# J3.net
KiCad netlist of a schematic drawn in Altium Designer
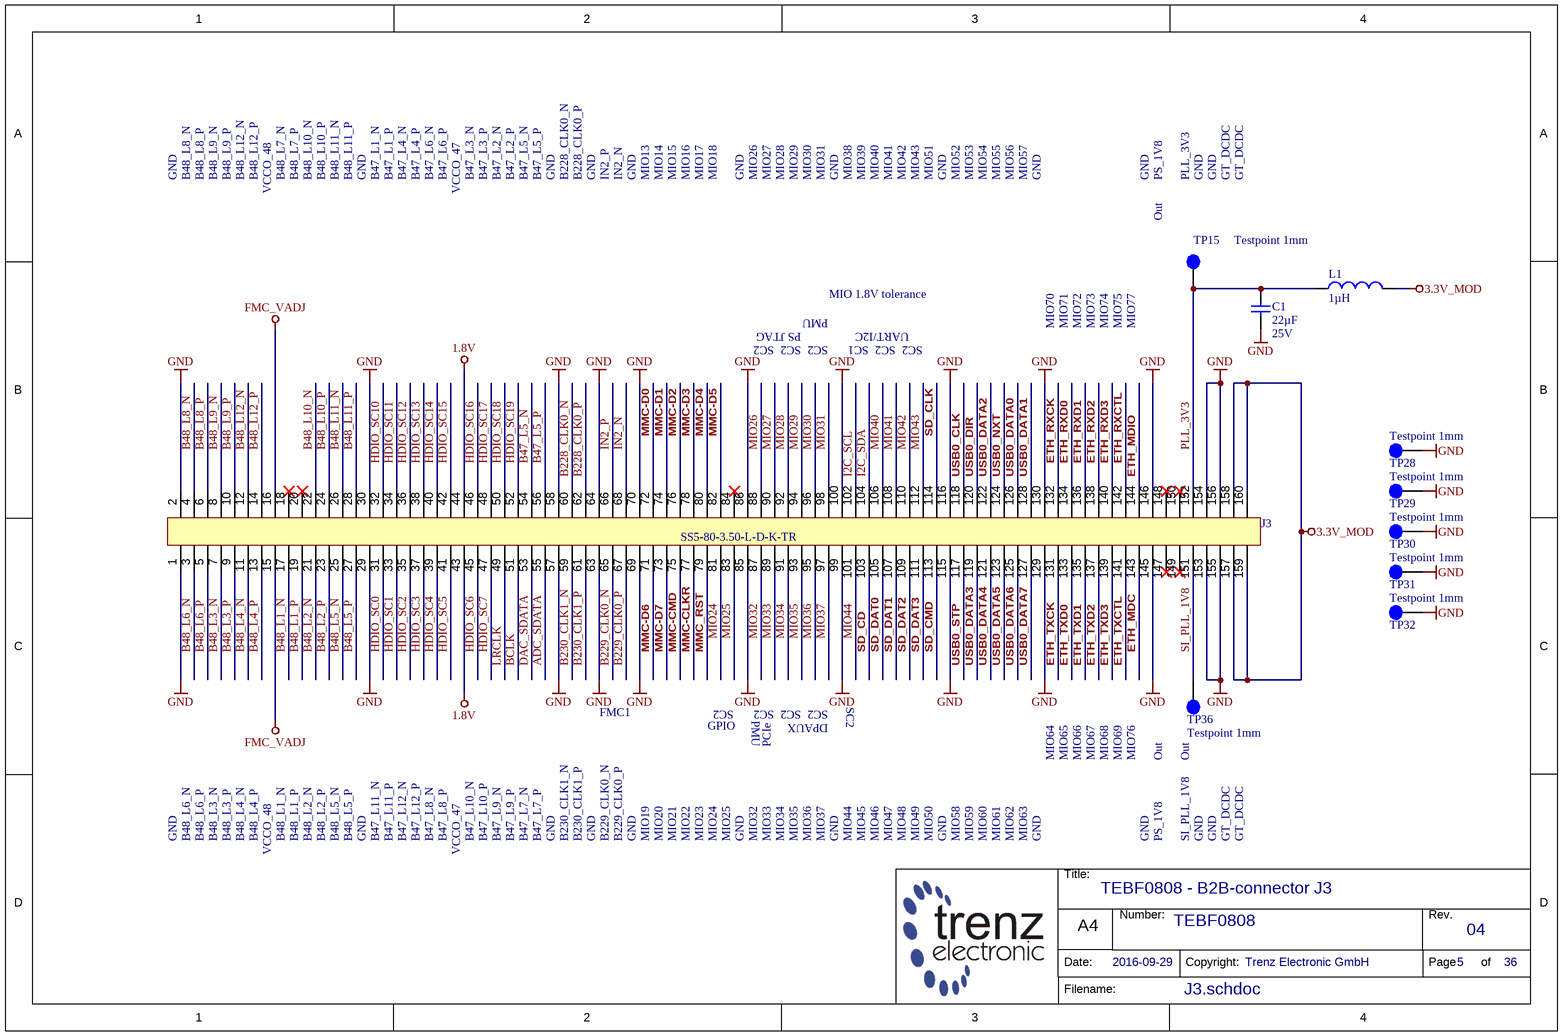
[diagram p0: J3.schdoc]

(export (version "E")
  (design (tool "Eeschema 10.0.6"))
  (components
    (comp (ref "C1")
      (value "22µF")
      (footprint "CAPC3216X180N")
      (description "KON 22µF X5R 25V SMD 10%")
      (fields (field (name "VOLTAGE") "25V") (field (name "TOLERANCE") "10%"))
      (libsource (lib "TE") (part "CAP-NP"))
    )
    (comp (ref "J3")
      (value "SS5-80-3.50-L-D-K-TR")
      (footprint "SS5-80-3.50-L-D-K-TR")
      (description "Samtec Ultra Fine Pitch Socket REF192552-01, 160 Pins")
      (libsource (lib "TE") (part "CON-160"))
    )
    (comp (ref "L1")
      (value "1µH")
      (footprint "INDC2520X100N")
      (description "IND SMD 1µH +-20% 0.055Ohm")
      (fields (field (name "VOLTAGE") "1.7A"))
      (libsource (lib "TE") (part "IND"))
    )
    (comp (ref "TP15") (value "Testpoint 1mm") (footprint "TP_1mm") (libsource (lib "TE") (part "TP")))
    (comp (ref "TP28") (value "Testpoint 1mm") (footprint "TP_1mm") (libsource (lib "TE") (part "TP")))
    (comp (ref "TP29") (value "Testpoint 1mm") (footprint "TP_1mm") (libsource (lib "TE") (part "TP")))
    (comp (ref "TP30") (value "Testpoint 1mm") (footprint "TP_1mm") (libsource (lib "TE") (part "TP")))
    (comp (ref "TP31") (value "Testpoint 1mm") (footprint "TP_1mm") (libsource (lib "TE") (part "TP")))
    (comp (ref "TP32") (value "Testpoint 1mm") (footprint "TP_1mm") (libsource (lib "TE") (part "TP")))
    (comp (ref "TP36") (value "Testpoint 1mm") (footprint "TP_1mm") (libsource (lib "TE") (part "TP")))
  )
  (nets
    (net (code "1") (name "/ADC_SDATA") (class "Default")
      (node (ref "J3") (pin "55") (pinfunction "55_55") (pintype "passive"))
    )
    (net (code "2") (name "/B47_L5_N") (class "Default")
      (node (ref "J3") (pin "54") (pinfunction "54_54") (pintype "passive"))
    )
    (net (code "3") (name "/B47_L5_P") (class "Default")
      (node (ref "J3") (pin "56") (pinfunction "56_56") (pintype "passive"))
    )
    (net (code "4") (name "/B48_L1_N") (class "Default")
      (node (ref "J3") (pin "17") (pinfunction "17_17") (pintype "passive"))
    )
    (net (code "5") (name "/B48_L1_P") (class "Default")
      (node (ref "J3") (pin "19") (pinfunction "19_19") (pintype "passive"))
    )
    (net (code "6") (name "/B48_L2_N") (class "Default")
      (node (ref "J3") (pin "21") (pinfunction "21_21") (pintype "passive"))
    )
    (net (code "7") (name "/B48_L2_P") (class "Default")
      (node (ref "J3") (pin "23") (pinfunction "23_23") (pintype "passive"))
    )
    (net (code "8") (name "/B48_L3_N") (class "Default")
      (node (ref "J3") (pin "7") (pinfunction "7_7") (pintype "passive"))
    )
    (net (code "9") (name "/B48_L3_P") (class "Default")
      (node (ref "J3") (pin "9") (pinfunction "9_9") (pintype "passive"))
    )
    (net (code "10") (name "/B48_L4_N") (class "Default")
      (node (ref "J3") (pin "11") (pinfunction "11_11") (pintype "passive"))
    )
    (net (code "11") (name "/B48_L4_P") (class "Default")
      (node (ref "J3") (pin "13") (pinfunction "13_13") (pintype "passive"))
    )
    (net (code "12") (name "/B48_L5_N") (class "Default")
      (node (ref "J3") (pin "25") (pinfunction "25_25") (pintype "passive"))
    )
    (net (code "13") (name "/B48_L5_P") (class "Default")
      (node (ref "J3") (pin "27") (pinfunction "27_27") (pintype "passive"))
    )
    (net (code "14") (name "/B48_L6_N") (class "Default")
      (node (ref "J3") (pin "3") (pinfunction "3_3") (pintype "passive"))
    )
    (net (code "15") (name "/B48_L6_P") (class "Default")
      (node (ref "J3") (pin "5") (pinfunction "5_5") (pintype "passive"))
    )
    (net (code "16") (name "/B48_L8_N") (class "Default")
      (node (ref "J3") (pin "4") (pinfunction "4_4") (pintype "passive"))
    )
    (net (code "17") (name "/B48_L8_P") (class "Default")
      (node (ref "J3") (pin "6") (pinfunction "6_6") (pintype "passive"))
    )
    (net (code "18") (name "/B48_L9_N") (class "Default")
      (node (ref "J3") (pin "8") (pinfunction "8_8") (pintype "passive"))
    )
    (net (code "19") (name "/B48_L9_P") (class "Default")
      (node (ref "J3") (pin "10") (pinfunction "10_10") (pintype "passive"))
    )
    (net (code "20") (name "/B48_L10_N") (class "Default")
      (node (ref "J3") (pin "22") (pinfunction "22_22") (pintype "passive"))
    )
    (net (code "21") (name "/B48_L10_P") (class "Default")
      (node (ref "J3") (pin "24") (pinfunction "24_24") (pintype "passive"))
    )
    (net (code "22") (name "/B48_L11_N") (class "Default")
      (node (ref "J3") (pin "26") (pinfunction "26_26") (pintype "passive"))
    )
    (net (code "23") (name "/B48_L11_P") (class "Default")
      (node (ref "J3") (pin "28") (pinfunction "28_28") (pintype "passive"))
    )
    (net (code "24") (name "/B48_L12_N") (class "Default")
      (node (ref "J3") (pin "12") (pinfunction "12_12") (pintype "passive"))
    )
    (net (code "25") (name "/B48_L12_P") (class "Default")
      (node (ref "J3") (pin "14") (pinfunction "14_14") (pintype "passive"))
    )
    (net (code "26") (name "/B228_CLK0_N") (class "Default")
      (node (ref "J3") (pin "60") (pinfunction "60_60") (pintype "passive"))
    )
    (net (code "27") (name "/B228_CLK0_P") (class "Default")
      (node (ref "J3") (pin "62") (pinfunction "62_62") (pintype "passive"))
    )
    (net (code "28") (name "/B229_CLK0_N") (class "Default")
      (node (ref "J3") (pin "65") (pinfunction "65_65") (pintype "passive"))
    )
    (net (code "29") (name "/B229_CLK0_P") (class "Default")
      (node (ref "J3") (pin "67") (pinfunction "67_67") (pintype "passive"))
    )
    (net (code "30") (name "/B230_CLK1_N") (class "Default")
      (node (ref "J3") (pin "59") (pinfunction "59_59") (pintype "passive"))
    )
    (net (code "31") (name "/B230_CLK1_P") (class "Default")
      (node (ref "J3") (pin "61") (pinfunction "61_61") (pintype "passive"))
    )
    (net (code "32") (name "/BCLK") (class "Default")
      (node (ref "J3") (pin "51") (pinfunction "51_51") (pintype "passive"))
    )
    (net (code "33") (name "/DAC_SDATA") (class "Default")
      (node (ref "J3") (pin "53") (pinfunction "53_53") (pintype "passive"))
    )
    (net (code "34") (name "/ETH_MDC") (class "Default")
      (node (ref "J3") (pin "143") (pinfunction "143_143") (pintype "passive"))
    )
    (net (code "35") (name "/ETH_MDIO") (class "Default")
      (node (ref "J3") (pin "144") (pinfunction "144_144") (pintype "passive"))
    )
    (net (code "36") (name "/ETH_RXCK") (class "Default")
      (node (ref "J3") (pin "132") (pinfunction "132_132") (pintype "passive"))
    )
    (net (code "37") (name "/ETH_RXCTL") (class "Default")
      (node (ref "J3") (pin "142") (pinfunction "142_142") (pintype "passive"))
    )
    (net (code "38") (name "/ETH_RXD0") (class "Default")
      (node (ref "J3") (pin "134") (pinfunction "134_134") (pintype "passive"))
    )
    (net (code "39") (name "/ETH_RXD1") (class "Default")
      (node (ref "J3") (pin "136") (pinfunction "136_136") (pintype "passive"))
    )
    (net (code "40") (name "/ETH_RXD2") (class "Default")
      (node (ref "J3") (pin "138") (pinfunction "138_138") (pintype "passive"))
    )
    (net (code "41") (name "/ETH_RXD3") (class "Default")
      (node (ref "J3") (pin "140") (pinfunction "140_140") (pintype "passive"))
    )
    (net (code "42") (name "/ETH_TXCK") (class "Default")
      (node (ref "J3") (pin "131") (pinfunction "131_131") (pintype "passive"))
    )
    (net (code "43") (name "/ETH_TXCTL") (class "Default")
      (node (ref "J3") (pin "141") (pinfunction "141_141") (pintype "passive"))
    )
    (net (code "44") (name "/ETH_TXD0") (class "Default")
      (node (ref "J3") (pin "133") (pinfunction "133_133") (pintype "passive"))
    )
    (net (code "45") (name "/ETH_TXD1") (class "Default")
      (node (ref "J3") (pin "135") (pinfunction "135_135") (pintype "passive"))
    )
    (net (code "46") (name "/ETH_TXD2") (class "Default")
      (node (ref "J3") (pin "137") (pinfunction "137_137") (pintype "passive"))
    )
    (net (code "47") (name "/ETH_TXD3") (class "Default")
      (node (ref "J3") (pin "139") (pinfunction "139_139") (pintype "passive"))
    )
    (net (code "48") (name "/HDIO_SC0") (class "Default")
      (node (ref "J3") (pin "31") (pinfunction "31_31") (pintype "passive"))
    )
    (net (code "49") (name "/HDIO_SC1") (class "Default")
      (node (ref "J3") (pin "33") (pinfunction "33_33") (pintype "passive"))
    )
    (net (code "50") (name "/HDIO_SC2") (class "Default")
      (node (ref "J3") (pin "35") (pinfunction "35_35") (pintype "passive"))
    )
    (net (code "51") (name "/HDIO_SC3") (class "Default")
      (node (ref "J3") (pin "37") (pinfunction "37_37") (pintype "passive"))
    )
    (net (code "52") (name "/HDIO_SC4") (class "Default")
      (node (ref "J3") (pin "39") (pinfunction "39_39") (pintype "passive"))
    )
    (net (code "53") (name "/HDIO_SC5") (class "Default")
      (node (ref "J3") (pin "41") (pinfunction "41_41") (pintype "passive"))
    )
    (net (code "54") (name "/HDIO_SC6") (class "Default")
      (node (ref "J3") (pin "45") (pinfunction "45_45") (pintype "passive"))
    )
    (net (code "55") (name "/HDIO_SC7") (class "Default")
      (node (ref "J3") (pin "47") (pinfunction "47_47") (pintype "passive"))
    )
    (net (code "56") (name "/HDIO_SC10") (class "Default")
      (node (ref "J3") (pin "32") (pinfunction "32_32") (pintype "passive"))
    )
    (net (code "57") (name "/HDIO_SC11") (class "Default")
      (node (ref "J3") (pin "34") (pinfunction "34_34") (pintype "passive"))
    )
    (net (code "58") (name "/HDIO_SC12") (class "Default")
      (node (ref "J3") (pin "36") (pinfunction "36_36") (pintype "passive"))
    )
    (net (code "59") (name "/HDIO_SC13") (class "Default")
      (node (ref "J3") (pin "38") (pinfunction "38_38") (pintype "passive"))
    )
    (net (code "60") (name "/HDIO_SC14") (class "Default")
      (node (ref "J3") (pin "40") (pinfunction "40_40") (pintype "passive"))
    )
    (net (code "61") (name "/HDIO_SC15") (class "Default")
      (node (ref "J3") (pin "42") (pinfunction "42_42") (pintype "passive"))
    )
    (net (code "62") (name "/HDIO_SC16") (class "Default")
      (node (ref "J3") (pin "46") (pinfunction "46_46") (pintype "passive"))
    )
    (net (code "63") (name "/HDIO_SC17") (class "Default")
      (node (ref "J3") (pin "48") (pinfunction "48_48") (pintype "passive"))
    )
    (net (code "64") (name "/HDIO_SC18") (class "Default")
      (node (ref "J3") (pin "50") (pinfunction "50_50") (pintype "passive"))
    )
    (net (code "65") (name "/HDIO_SC19") (class "Default")
      (node (ref "J3") (pin "52") (pinfunction "52_52") (pintype "passive"))
    )
    (net (code "66") (name "/I2C_SCL") (class "Default")
      (node (ref "J3") (pin "102") (pinfunction "102_102") (pintype "passive"))
    )
    (net (code "67") (name "/I2C_SDA") (class "Default")
      (node (ref "J3") (pin "104") (pinfunction "104_104") (pintype "passive"))
    )
    (net (code "68") (name "/IN2_N") (class "Default")
      (node (ref "J3") (pin "68") (pinfunction "68_68") (pintype "passive"))
    )
    (net (code "69") (name "/IN2_P") (class "Default")
      (node (ref "J3") (pin "66") (pinfunction "66_66") (pintype "passive"))
    )
    (net (code "70") (name "/LRCLK") (class "Default")
      (node (ref "J3") (pin "49") (pinfunction "49_49") (pintype "passive"))
    )
    (net (code "71") (name "/MIO24") (class "Default")
      (node (ref "J3") (pin "81") (pinfunction "81_81") (pintype "passive"))
    )
    (net (code "72") (name "/MIO25") (class "Default")
      (node (ref "J3") (pin "83") (pinfunction "83_83") (pintype "passive"))
    )
    (net (code "73") (name "/MIO26") (class "Default")
      (node (ref "J3") (pin "88") (pinfunction "88_88") (pintype "passive"))
    )
    (net (code "74") (name "/MIO27") (class "Default")
      (node (ref "J3") (pin "90") (pinfunction "90_90") (pintype "passive"))
    )
    (net (code "75") (name "/MIO28") (class "Default")
      (node (ref "J3") (pin "92") (pinfunction "92_92") (pintype "passive"))
    )
    (net (code "76") (name "/MIO29") (class "Default")
      (node (ref "J3") (pin "94") (pinfunction "94_94") (pintype "passive"))
    )
    (net (code "77") (name "/MIO30") (class "Default")
      (node (ref "J3") (pin "96") (pinfunction "96_96") (pintype "passive"))
    )
    (net (code "78") (name "/MIO31") (class "Default")
      (node (ref "J3") (pin "98") (pinfunction "98_98") (pintype "passive"))
    )
    (net (code "79") (name "/MIO32") (class "Default")
      (node (ref "J3") (pin "87") (pinfunction "87_87") (pintype "passive"))
    )
    (net (code "80") (name "/MIO33") (class "Default")
      (node (ref "J3") (pin "89") (pinfunction "89_89") (pintype "passive"))
    )
    (net (code "81") (name "/MIO34") (class "Default")
      (node (ref "J3") (pin "91") (pinfunction "91_91") (pintype "passive"))
    )
    (net (code "82") (name "/MIO35") (class "Default")
      (node (ref "J3") (pin "93") (pinfunction "93_93") (pintype "passive"))
    )
    (net (code "83") (name "/MIO36") (class "Default")
      (node (ref "J3") (pin "95") (pinfunction "95_95") (pintype "passive"))
    )
    (net (code "84") (name "/MIO37") (class "Default")
      (node (ref "J3") (pin "97") (pinfunction "97_97") (pintype "passive"))
    )
    (net (code "85") (name "/MIO40") (class "Default")
      (node (ref "J3") (pin "106") (pinfunction "106_106") (pintype "passive"))
    )
    (net (code "86") (name "/MIO41") (class "Default")
      (node (ref "J3") (pin "108") (pinfunction "108_108") (pintype "passive"))
    )
    (net (code "87") (name "/MIO42") (class "Default")
      (node (ref "J3") (pin "110") (pinfunction "110_110") (pintype "passive"))
    )
    (net (code "88") (name "/MIO43") (class "Default")
      (node (ref "J3") (pin "112") (pinfunction "112_112") (pintype "passive"))
    )
    (net (code "89") (name "/MIO44") (class "Default")
      (node (ref "J3") (pin "101") (pinfunction "101_101") (pintype "passive"))
    )
    (net (code "90") (name "/MMC-CLKR") (class "Default")
      (node (ref "J3") (pin "77") (pinfunction "77_77") (pintype "passive"))
    )
    (net (code "91") (name "/MMC-CMD") (class "Default")
      (node (ref "J3") (pin "75") (pinfunction "75_75") (pintype "passive"))
    )
    (net (code "92") (name "/MMC-D0") (class "Default")
      (node (ref "J3") (pin "72") (pinfunction "72_72") (pintype "passive"))
    )
    (net (code "93") (name "/MMC-D1") (class "Default")
      (node (ref "J3") (pin "74") (pinfunction "74_74") (pintype "passive"))
    )
    (net (code "94") (name "/MMC-D2") (class "Default")
      (node (ref "J3") (pin "76") (pinfunction "76_76") (pintype "passive"))
    )
    (net (code "95") (name "/MMC-D3") (class "Default")
      (node (ref "J3") (pin "78") (pinfunction "78_78") (pintype "passive"))
    )
    (net (code "96") (name "/MMC-D4") (class "Default")
      (node (ref "J3") (pin "80") (pinfunction "80_80") (pintype "passive"))
    )
    (net (code "97") (name "/MMC-D5") (class "Default")
      (node (ref "J3") (pin "82") (pinfunction "82_82") (pintype "passive"))
    )
    (net (code "98") (name "/MMC-D6") (class "Default")
      (node (ref "J3") (pin "71") (pinfunction "71_71") (pintype "passive"))
    )
    (net (code "99") (name "/MMC-D7") (class "Default")
      (node (ref "J3") (pin "73") (pinfunction "73_73") (pintype "passive"))
    )
    (net (code "100") (name "/MMC_RST") (class "Default")
      (node (ref "J3") (pin "79") (pinfunction "79_79") (pintype "passive"))
    )
    (net (code "101") (name "/PLL_3V3") (class "Default")
      (node (ref "C1") (pin "2") (pinfunction "2_2") (pintype "passive"))
      (node (ref "J3") (pin "152") (pinfunction "152_152") (pintype "passive"))
      (node (ref "L1") (pin "1") (pinfunction "1_1") (pintype "passive"))
      (node (ref "TP15") (pin "1") (pintype "passive"))
    )
    (net (code "102") (name "/SD_CD") (class "Default")
      (node (ref "J3") (pin "103") (pinfunction "103_103") (pintype "passive"))
    )
    (net (code "103") (name "/SD_CLK") (class "Default")
      (node (ref "J3") (pin "114") (pinfunction "114_114") (pintype "passive"))
    )
    (net (code "104") (name "/SD_CMD") (class "Default")
      (node (ref "J3") (pin "113") (pinfunction "113_113") (pintype "passive"))
    )
    (net (code "105") (name "/SD_DAT0") (class "Default")
      (node (ref "J3") (pin "105") (pinfunction "105_105") (pintype "passive"))
    )
    (net (code "106") (name "/SD_DAT1") (class "Default")
      (node (ref "J3") (pin "107") (pinfunction "107_107") (pintype "passive"))
    )
    (net (code "107") (name "/SD_DAT2") (class "Default")
      (node (ref "J3") (pin "109") (pinfunction "109_109") (pintype "passive"))
    )
    (net (code "108") (name "/SD_DAT3") (class "Default")
      (node (ref "J3") (pin "111") (pinfunction "111_111") (pintype "passive"))
    )
    (net (code "109") (name "/SI_PLL_1V8") (class "Default")
      (node (ref "J3") (pin "151") (pinfunction "151_151") (pintype "passive"))
      (node (ref "TP36") (pin "1") (pintype "passive"))
    )
    (net (code "110") (name "/USB0_CLK") (class "Default")
      (node (ref "J3") (pin "118") (pinfunction "118_118") (pintype "passive"))
    )
    (net (code "111") (name "/USB0_DATA0") (class "Default")
      (node (ref "J3") (pin "126") (pinfunction "126_126") (pintype "passive"))
    )
    (net (code "112") (name "/USB0_DATA1") (class "Default")
      (node (ref "J3") (pin "128") (pinfunction "128_128") (pintype "passive"))
    )
    (net (code "113") (name "/USB0_DATA2") (class "Default")
      (node (ref "J3") (pin "122") (pinfunction "122_122") (pintype "passive"))
    )
    (net (code "114") (name "/USB0_DATA3") (class "Default")
      (node (ref "J3") (pin "119") (pinfunction "119_119") (pintype "passive"))
    )
    (net (code "115") (name "/USB0_DATA4") (class "Default")
      (node (ref "J3") (pin "121") (pinfunction "121_121") (pintype "passive"))
    )
    (net (code "116") (name "/USB0_DATA5") (class "Default")
      (node (ref "J3") (pin "123") (pinfunction "123_123") (pintype "passive"))
    )
    (net (code "117") (name "/USB0_DATA6") (class "Default")
      (node (ref "J3") (pin "125") (pinfunction "125_125") (pintype "passive"))
    )
    (net (code "118") (name "/USB0_DATA7") (class "Default")
      (node (ref "J3") (pin "127") (pinfunction "127_127") (pintype "passive"))
    )
    (net (code "119") (name "/USB0_DIR") (class "Default")
      (node (ref "J3") (pin "120") (pinfunction "120_120") (pintype "passive"))
    )
    (net (code "120") (name "/USB0_NXT") (class "Default")
      (node (ref "J3") (pin "124") (pinfunction "124_124") (pintype "passive"))
    )
    (net (code "121") (name "/USB0_STP") (class "Default")
      (node (ref "J3") (pin "117") (pinfunction "117_117") (pintype "passive"))
    )
    (net (code "122") (name "1.8V") (class "Default")
      (node (ref "J3") (pin "43") (pinfunction "43_43") (pintype "passive"))
      (node (ref "J3") (pin "44") (pinfunction "44_44") (pintype "passive"))
    )
    (net (code "123") (name "3.3V_MOD") (class "Default")
      (node (ref "J3") (pin "157") (pinfunction "157_157") (pintype "passive"))
      (node (ref "J3") (pin "158") (pinfunction "158_158") (pintype "passive"))
      (node (ref "J3") (pin "159") (pinfunction "159_159") (pintype "passive"))
      (node (ref "J3") (pin "160") (pinfunction "160_160") (pintype "passive"))
      (node (ref "L1") (pin "2") (pinfunction "2_2") (pintype "passive"))
    )
    (net (code "124") (name "FMC_VADJ") (class "Default")
      (node (ref "J3") (pin "15") (pinfunction "15_15") (pintype "passive"))
      (node (ref "J3") (pin "16") (pinfunction "16_16") (pintype "passive"))
    )
    (net (code "125") (name "GND") (class "Default")
      (node (ref "C1") (pin "1") (pinfunction "1_1") (pintype "passive"))
      (node (ref "J3") (pin "1") (pinfunction "1_1") (pintype "passive"))
      (node (ref "J3") (pin "100") (pinfunction "100_100") (pintype "passive"))
      (node (ref "J3") (pin "115") (pinfunction "115_115") (pintype "passive"))
      (node (ref "J3") (pin "116") (pinfunction "116_116") (pintype "passive"))
      (node (ref "J3") (pin "129") (pinfunction "129_129") (pintype "passive"))
      (node (ref "J3") (pin "130") (pinfunction "130_130") (pintype "passive"))
      (node (ref "J3") (pin "145") (pinfunction "145_145") (pintype "passive"))
      (node (ref "J3") (pin "146") (pinfunction "146_146") (pintype "passive"))
      (node (ref "J3") (pin "153") (pinfunction "153_153") (pintype "passive"))
      (node (ref "J3") (pin "154") (pinfunction "154_154") (pintype "passive"))
      (node (ref "J3") (pin "155") (pinfunction "155_155") (pintype "passive"))
      (node (ref "J3") (pin "156") (pinfunction "156_156") (pintype "passive"))
      (node (ref "J3") (pin "2") (pinfunction "2_2") (pintype "passive"))
      (node (ref "J3") (pin "29") (pinfunction "29_29") (pintype "passive"))
      (node (ref "J3") (pin "30") (pinfunction "30_30") (pintype "passive"))
      (node (ref "J3") (pin "57") (pinfunction "57_57") (pintype "passive"))
      (node (ref "J3") (pin "58") (pinfunction "58_58") (pintype "passive"))
      (node (ref "J3") (pin "63") (pinfunction "63_63") (pintype "passive"))
      (node (ref "J3") (pin "64") (pinfunction "64_64") (pintype "passive"))
      (node (ref "J3") (pin "69") (pinfunction "69_69") (pintype "passive"))
      (node (ref "J3") (pin "70") (pinfunction "70_70") (pintype "passive"))
      (node (ref "J3") (pin "85") (pinfunction "85_85") (pintype "passive"))
      (node (ref "J3") (pin "86") (pinfunction "86_86") (pintype "passive"))
      (node (ref "J3") (pin "99") (pinfunction "99_99") (pintype "passive"))
      (node (ref "TP28") (pin "1") (pintype "passive"))
      (node (ref "TP29") (pin "1") (pintype "passive"))
      (node (ref "TP30") (pin "1") (pintype "passive"))
      (node (ref "TP31") (pin "1") (pintype "passive"))
      (node (ref "TP32") (pin "1") (pintype "passive"))
    )
    (net (code "126") (name "unconnected-(J3-Pad18)") (class "Default")
      (node (ref "J3") (pin "18") (pinfunction "18_18") (pintype "passive+no_connect"))
    )
    (net (code "127") (name "unconnected-(J3-Pad20)") (class "Default")
      (node (ref "J3") (pin "20") (pinfunction "20_20") (pintype "passive+no_connect"))
    )
    (net (code "128") (name "unconnected-(J3-Pad84)") (class "Default")
      (node (ref "J3") (pin "84") (pinfunction "84_84") (pintype "passive+no_connect"))
    )
    (net (code "129") (name "unconnected-(J3-Pad147)") (class "Default")
      (node (ref "J3") (pin "147") (pinfunction "147_147") (pintype "passive+no_connect"))
    )
    (net (code "130") (name "unconnected-(J3-Pad148)") (class "Default")
      (node (ref "J3") (pin "148") (pinfunction "148_148") (pintype "passive+no_connect"))
    )
    (net (code "131") (name "unconnected-(J3-Pad149)") (class "Default")
      (node (ref "J3") (pin "149") (pinfunction "149_149") (pintype "passive+no_connect"))
    )
    (net (code "132") (name "unconnected-(J3-Pad150)") (class "Default")
      (node (ref "J3") (pin "150") (pinfunction "150_150") (pintype "passive+no_connect"))
    )
  )
)
